# Selectric_Terminal.net
KiCad netlist of a schematic drawn in EasyEDA Pro
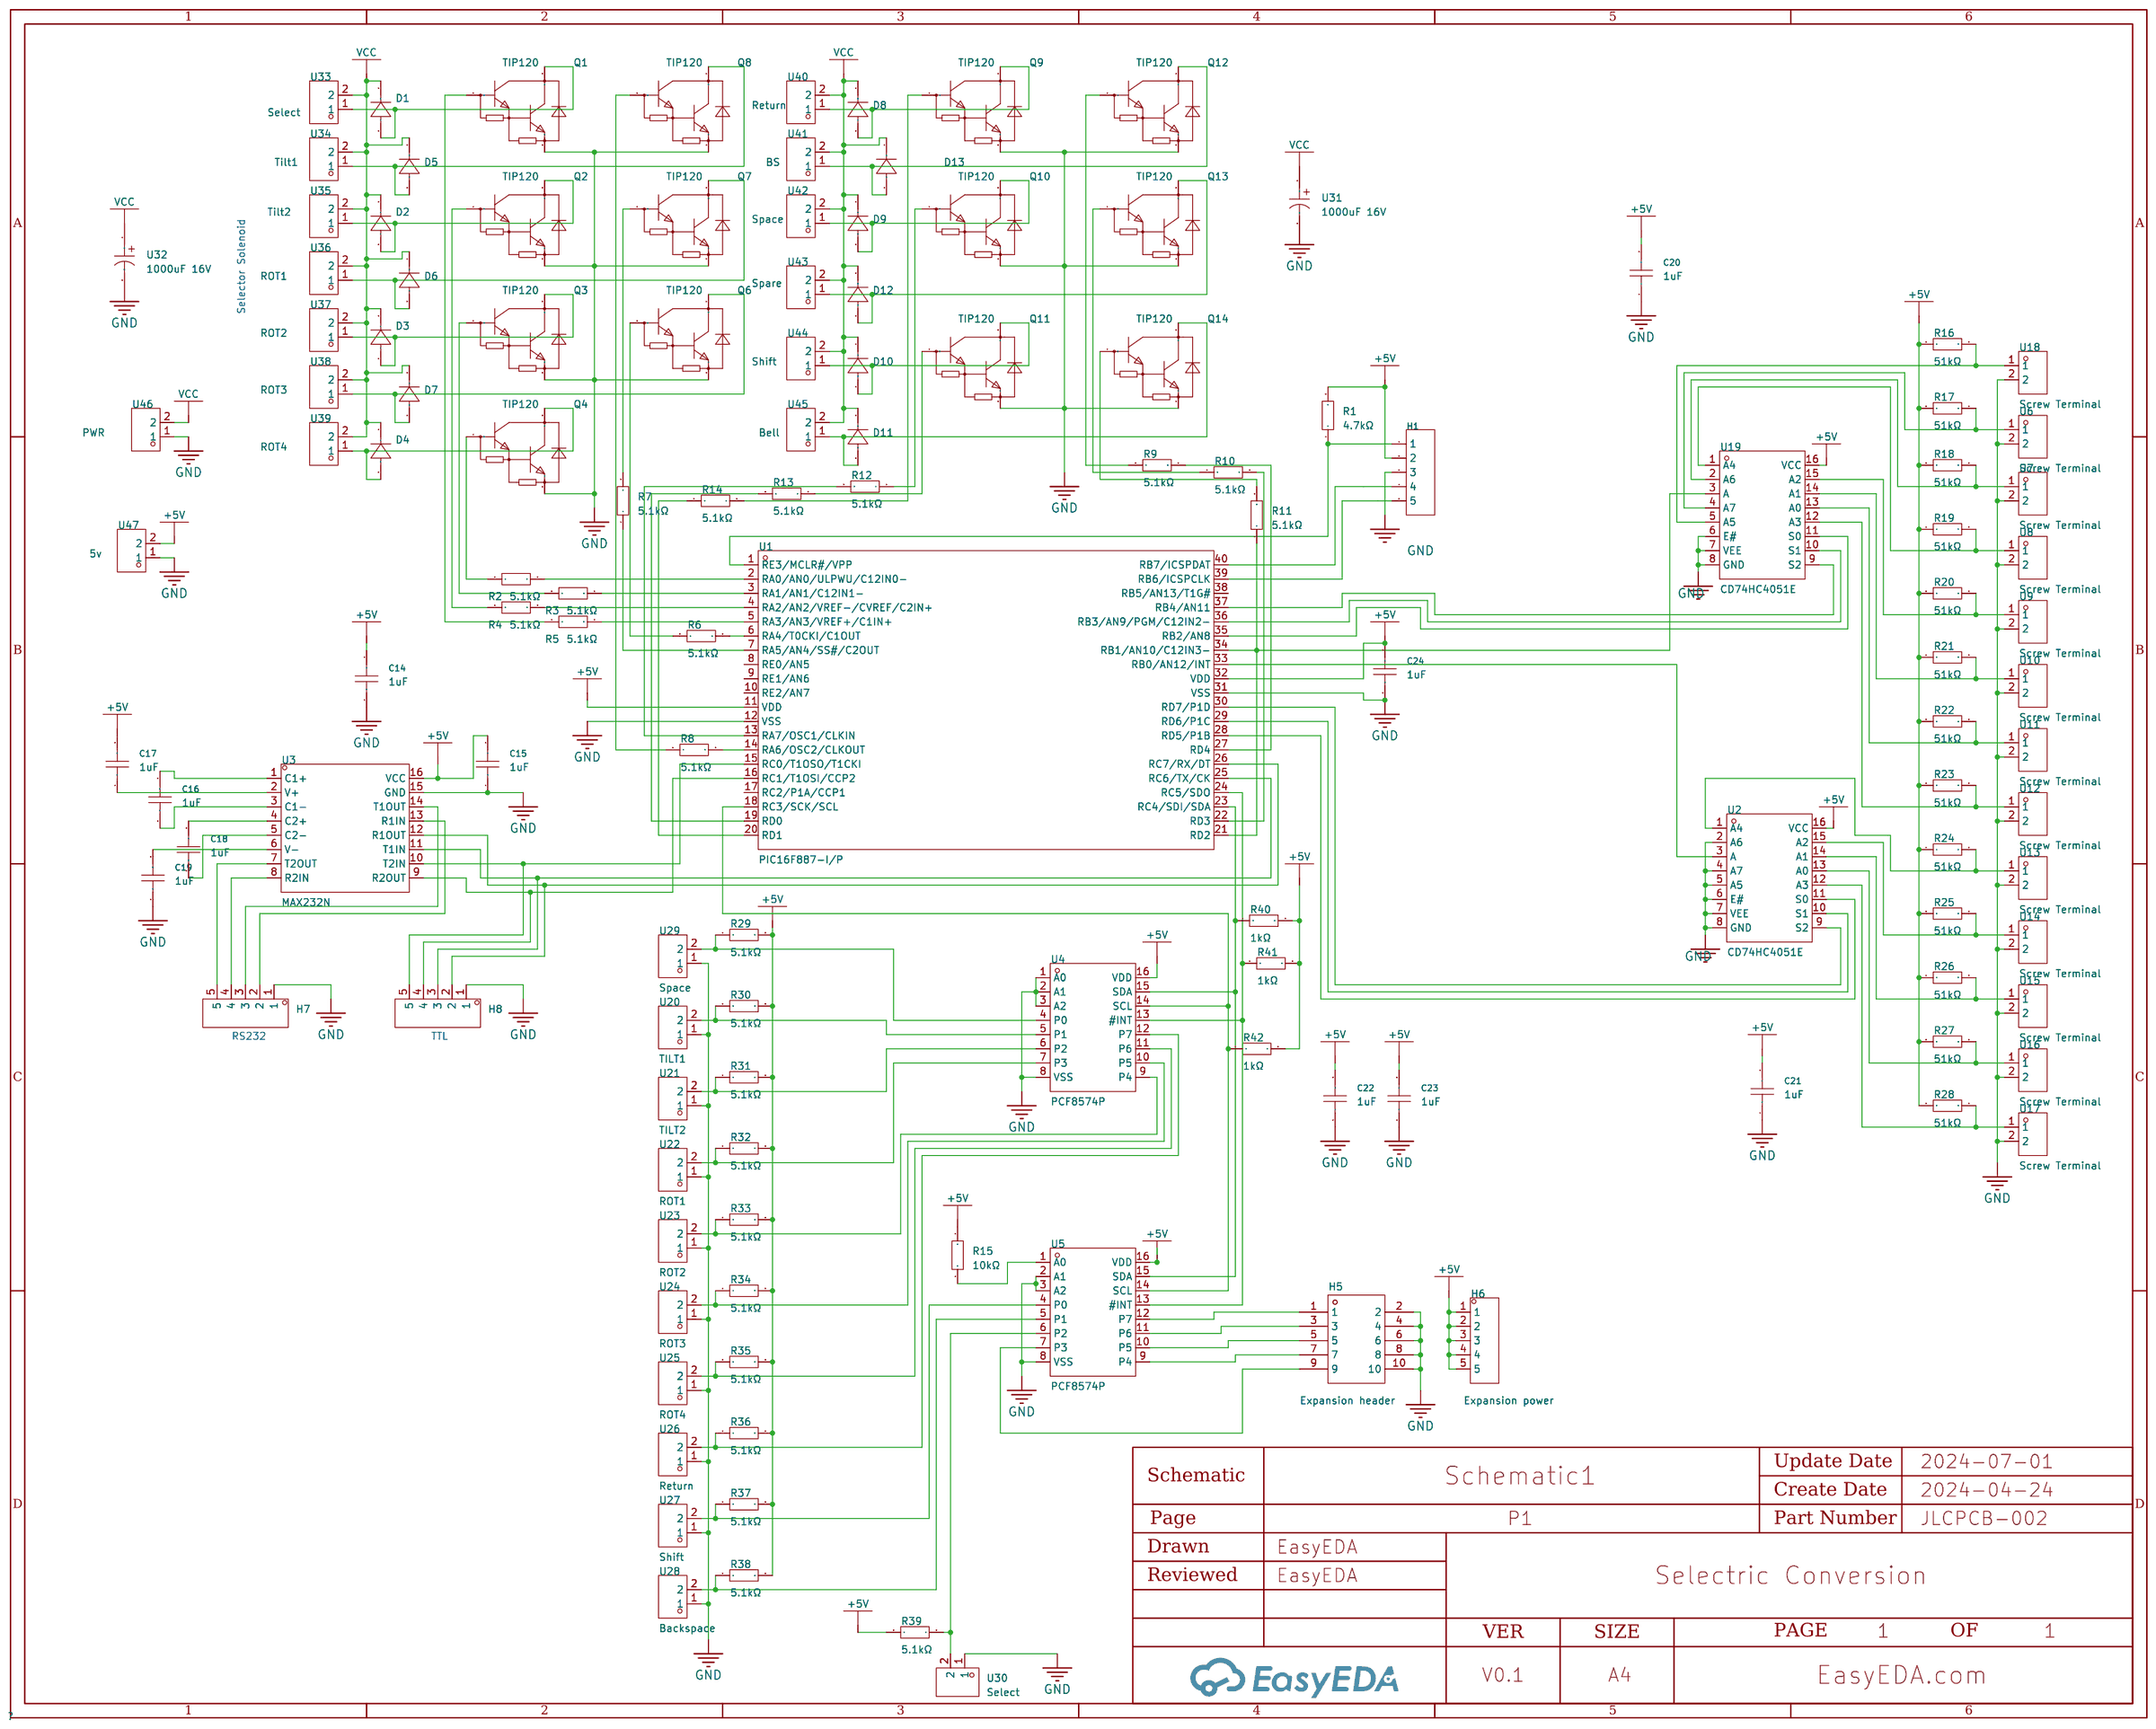
[diagram p0: schematic sheet]

(export (version "E")
  (design (tool "Eeschema 10.0.6"))
  (components
    (comp (ref "C14")
      (value "1uF")
      (footprint "easyedapro:CAP-TH_L5.0-W2.5-P5.00-D1.0")
      (fields
        (field (name "Manufacturer Part") "CC1H104MC1FD3F6C10MF")
        (field (name "Manufacturer") "Dersonic(德尔创)")
      )
      (libsource (lib "easyedapro") (part "CC1H104MC1FD3F6C10MF"))
    )
    (comp (ref "C15")
      (value "1uF")
      (footprint "easyedapro:CAP-TH_L5.0-W2.5-P5.00-D1.0")
      (fields
        (field (name "Manufacturer Part") "CC1H104MC1FD3F6C10MF")
        (field (name "Manufacturer") "Dersonic(德尔创)")
      )
      (libsource (lib "easyedapro") (part "CC1H104MC1FD3F6C10MF"))
    )
    (comp (ref "C16")
      (value "1uF")
      (footprint "easyedapro:CAP-TH_L5.0-W2.5-P5.00-D1.0")
      (fields
        (field (name "Manufacturer Part") "CC1H104MC1FD3F6C10MF")
        (field (name "Manufacturer") "Dersonic(德尔创)")
      )
      (libsource (lib "easyedapro") (part "CC1H104MC1FD3F6C10MF"))
    )
    (comp (ref "C17")
      (value "1uF")
      (footprint "easyedapro:CAP-TH_L5.0-W2.5-P5.00-D1.0")
      (fields
        (field (name "Manufacturer Part") "CC1H104MC1FD3F6C10MF")
        (field (name "Manufacturer") "Dersonic(德尔创)")
      )
      (libsource (lib "easyedapro") (part "CC1H104MC1FD3F6C10MF"))
    )
    (comp (ref "C18")
      (value "1uF")
      (footprint "easyedapro:CAP-TH_L5.0-W2.5-P5.00-D1.0")
      (fields
        (field (name "Manufacturer Part") "CC1H104MC1FD3F6C10MF")
        (field (name "Manufacturer") "Dersonic(德尔创)")
      )
      (libsource (lib "easyedapro") (part "CC1H104MC1FD3F6C10MF"))
    )
    (comp (ref "C19")
      (value "1uF")
      (footprint "easyedapro:CAP-TH_L5.0-W2.5-P5.00-D1.0")
      (fields
        (field (name "Manufacturer Part") "CC1H104MC1FD3F6C10MF")
        (field (name "Manufacturer") "Dersonic(德尔创)")
      )
      (libsource (lib "easyedapro") (part "CC1H104MC1FD3F6C10MF"))
    )
    (comp (ref "C20")
      (value "1uF")
      (footprint "easyedapro:CAP-TH_L5.0-W2.5-P5.00-D1.0")
      (fields
        (field (name "Manufacturer Part") "CC1H104MC1FD3F6C10MF")
        (field (name "Manufacturer") "Dersonic(德尔创)")
      )
      (libsource (lib "easyedapro") (part "CC1H104MC1FD3F6C10MF"))
    )
    (comp (ref "C21")
      (value "1uF")
      (footprint "easyedapro:CAP-TH_L5.0-W2.5-P5.00-D1.0")
      (fields
        (field (name "Manufacturer Part") "CC1H104MC1FD3F6C10MF")
        (field (name "Manufacturer") "Dersonic(德尔创)")
      )
      (libsource (lib "easyedapro") (part "CC1H104MC1FD3F6C10MF"))
    )
    (comp (ref "C22")
      (value "1uF")
      (footprint "easyedapro:CAP-TH_L5.0-W2.5-P5.00-D1.0")
      (fields
        (field (name "Manufacturer Part") "CC1H104MC1FD3F6C10MF")
        (field (name "Manufacturer") "Dersonic(德尔创)")
      )
      (libsource (lib "easyedapro") (part "CC1H104MC1FD3F6C10MF"))
    )
    (comp (ref "C23")
      (value "1uF")
      (footprint "easyedapro:CAP-TH_L5.0-W2.5-P5.00-D1.0")
      (fields
        (field (name "Manufacturer Part") "CC1H104MC1FD3F6C10MF")
        (field (name "Manufacturer") "Dersonic(德尔创)")
      )
      (libsource (lib "easyedapro") (part "CC1H104MC1FD3F6C10MF"))
    )
    (comp (ref "C24")
      (value "1uF")
      (footprint "easyedapro:CAP-TH_L5.0-W2.5-P5.00-D1.0")
      (fields
        (field (name "Manufacturer Part") "CC1H104MC1FD3F6C10MF")
        (field (name "Manufacturer") "Dersonic(德尔创)")
      )
      (libsource (lib "easyedapro") (part "CC1H104MC1FD3F6C10MF"))
    )
    (comp (ref "D1")
      (value "~")
      (footprint "easyedapro:DO-41_BD2.4-L4.7-P8.70-D0.9-RD")
      (libsource (lib "easyedapro") (part "D_1N4007"))
    )
    (comp (ref "D2")
      (value "~")
      (footprint "easyedapro:DO-41_BD2.4-L4.7-P8.70-D0.9-RD")
      (libsource (lib "easyedapro") (part "D_1N4007"))
    )
    (comp (ref "D3")
      (value "~")
      (footprint "easyedapro:DO-41_BD2.4-L4.7-P8.70-D0.9-RD")
      (libsource (lib "easyedapro") (part "D_1N4007"))
    )
    (comp (ref "D4")
      (value "~")
      (footprint "easyedapro:DO-41_BD2.4-L4.7-P8.70-D0.9-RD")
      (libsource (lib "easyedapro") (part "D_1N4007"))
    )
    (comp (ref "D5")
      (value "~")
      (footprint "easyedapro:DO-41_BD2.4-L4.7-P8.70-D0.9-RD")
      (libsource (lib "easyedapro") (part "D_1N4007"))
    )
    (comp (ref "D6")
      (value "~")
      (footprint "easyedapro:DO-41_BD2.4-L4.7-P8.70-D0.9-RD")
      (libsource (lib "easyedapro") (part "D_1N4007"))
    )
    (comp (ref "D7")
      (value "~")
      (footprint "easyedapro:DO-41_BD2.4-L4.7-P8.70-D0.9-RD")
      (libsource (lib "easyedapro") (part "D_1N4007"))
    )
    (comp (ref "D8")
      (value "~")
      (footprint "easyedapro:DO-41_BD2.4-L4.7-P8.70-D0.9-RD")
      (libsource (lib "easyedapro") (part "D_1N4007"))
    )
    (comp (ref "D9")
      (value "~")
      (footprint "easyedapro:DO-41_BD2.4-L4.7-P8.70-D0.9-RD")
      (libsource (lib "easyedapro") (part "D_1N4007"))
    )
    (comp (ref "D10")
      (value "~")
      (footprint "easyedapro:DO-41_BD2.4-L4.7-P8.70-D0.9-RD")
      (libsource (lib "easyedapro") (part "D_1N4007"))
    )
    (comp (ref "D11")
      (value "~")
      (footprint "easyedapro:DO-41_BD2.4-L4.7-P8.70-D0.9-RD")
      (libsource (lib "easyedapro") (part "D_1N4007"))
    )
    (comp (ref "D12")
      (value "~")
      (footprint "easyedapro:DO-41_BD2.4-L4.7-P8.70-D0.9-RD")
      (libsource (lib "easyedapro") (part "D_1N4007"))
    )
    (comp (ref "D13")
      (value "~")
      (footprint "easyedapro:DO-41_BD2.4-L4.7-P8.70-D0.9-RD")
      (libsource (lib "easyedapro") (part "D_1N4007"))
    )
    (comp (ref "H1")
      (value "~")
      (footprint "easyedapro:HDR-TH_5P-P2.54-V-F")
      (libsource (lib "easyedapro") (part "Header-Female-2.54_1x5"))
    )
    (comp (ref "H5")
      (value "Expansion header")
      (footprint "easyedapro:HDR-TH_10P-P2.54-V-M-R2-C5-S2.54")
      (libsource (lib "easyedapro") (part "HDR-M-2.54_2x5"))
    )
    (comp (ref "H6")
      (value "Expansion power")
      (footprint "easyedapro:HDR-TH_5P-P2.54-V-M")
      (libsource (lib "easyedapro") (part "MTP125-1105S1"))
    )
    (comp (ref "H7")
      (value "~")
      (footprint "easyedapro:HDR-TH_5P-P2.54-V-M")
      (libsource (lib "easyedapro") (part "MTP125-1105S1"))
    )
    (comp (ref "H8")
      (value "~")
      (footprint "easyedapro:HDR-TH_5P-P2.54-V-M")
      (libsource (lib "easyedapro") (part "MTP125-1105S1"))
    )
    (comp (ref "Q1")
      (value "TIP120")
      (footprint "easyedapro:TO-220-3_L10.0-W4.5-P2.54-L")
      (fields (field (name "Manufacturer") "ST(意法半导体)"))
      (libsource (lib "easyedapro") (part "TIP120"))
    )
    (comp (ref "Q2")
      (value "TIP120")
      (footprint "easyedapro:TO-220-3_L10.0-W4.5-P2.54-L")
      (fields (field (name "Manufacturer") "ST(意法半导体)"))
      (libsource (lib "easyedapro") (part "TIP120"))
    )
    (comp (ref "Q3")
      (value "TIP120")
      (footprint "easyedapro:TO-220-3_L10.0-W4.5-P2.54-L")
      (fields (field (name "Manufacturer") "ST(意法半导体)"))
      (libsource (lib "easyedapro") (part "TIP120"))
    )
    (comp (ref "Q4")
      (value "TIP120")
      (footprint "easyedapro:TO-220-3_L10.0-W4.5-P2.54-L")
      (fields (field (name "Manufacturer") "ST(意法半导体)"))
      (libsource (lib "easyedapro") (part "TIP120"))
    )
    (comp (ref "Q6")
      (value "TIP120")
      (footprint "easyedapro:TO-220-3_L10.0-W4.5-P2.54-L")
      (fields (field (name "Manufacturer") "ST(意法半导体)"))
      (libsource (lib "easyedapro") (part "TIP120"))
    )
    (comp (ref "Q7")
      (value "TIP120")
      (footprint "easyedapro:TO-220-3_L10.0-W4.5-P2.54-L")
      (fields (field (name "Manufacturer") "ST(意法半导体)"))
      (libsource (lib "easyedapro") (part "TIP120"))
    )
    (comp (ref "Q8")
      (value "TIP120")
      (footprint "easyedapro:TO-220-3_L10.0-W4.5-P2.54-L")
      (fields (field (name "Manufacturer") "ST(意法半导体)"))
      (libsource (lib "easyedapro") (part "TIP120"))
    )
    (comp (ref "Q9")
      (value "TIP120")
      (footprint "easyedapro:TO-220-3_L10.0-W4.5-P2.54-L")
      (fields (field (name "Manufacturer") "ST(意法半导体)"))
      (libsource (lib "easyedapro") (part "TIP120"))
    )
    (comp (ref "Q10")
      (value "TIP120")
      (footprint "easyedapro:TO-220-3_L10.0-W4.5-P2.54-L")
      (fields (field (name "Manufacturer") "ST(意法半导体)"))
      (libsource (lib "easyedapro") (part "TIP120"))
    )
    (comp (ref "Q11")
      (value "TIP120")
      (footprint "easyedapro:TO-220-3_L10.0-W4.5-P2.54-L")
      (fields (field (name "Manufacturer") "ST(意法半导体)"))
      (libsource (lib "easyedapro") (part "TIP120"))
    )
    (comp (ref "Q12")
      (value "TIP120")
      (footprint "easyedapro:TO-220-3_L10.0-W4.5-P2.54-L")
      (fields (field (name "Manufacturer") "ST(意法半导体)"))
      (libsource (lib "easyedapro") (part "TIP120"))
    )
    (comp (ref "Q13")
      (value "TIP120")
      (footprint "easyedapro:TO-220-3_L10.0-W4.5-P2.54-L")
      (fields (field (name "Manufacturer") "ST(意法半导体)"))
      (libsource (lib "easyedapro") (part "TIP120"))
    )
    (comp (ref "Q14")
      (value "TIP120")
      (footprint "easyedapro:TO-220-3_L10.0-W4.5-P2.54-L")
      (fields (field (name "Manufacturer") "ST(意法半导体)"))
      (libsource (lib "easyedapro") (part "TIP120"))
    )
    (comp (ref "R1")
      (value "4.7kΩ")
      (footprint "easyedapro:R_AXIAL-0.4")
      (libsource (lib "easyedapro") (part "Res"))
    )
    (comp (ref "R2")
      (value "5.1kΩ")
      (footprint "easyedapro:R_AXIAL-0.4")
      (libsource (lib "easyedapro") (part "Res"))
    )
    (comp (ref "R3")
      (value "5.1kΩ")
      (footprint "easyedapro:R_AXIAL-0.4")
      (libsource (lib "easyedapro") (part "Res"))
    )
    (comp (ref "R4")
      (value "5.1kΩ")
      (footprint "easyedapro:R_AXIAL-0.4")
      (libsource (lib "easyedapro") (part "Res"))
    )
    (comp (ref "R5")
      (value "5.1kΩ")
      (footprint "easyedapro:R_AXIAL-0.4")
      (libsource (lib "easyedapro") (part "Res"))
    )
    (comp (ref "R6")
      (value "5.1kΩ")
      (footprint "easyedapro:R_AXIAL-0.4")
      (libsource (lib "easyedapro") (part "Res"))
    )
    (comp (ref "R7")
      (value "5.1kΩ")
      (footprint "easyedapro:R_AXIAL-0.4")
      (libsource (lib "easyedapro") (part "Res"))
    )
    (comp (ref "R8")
      (value "5.1kΩ")
      (footprint "easyedapro:R_AXIAL-0.4")
      (libsource (lib "easyedapro") (part "Res"))
    )
    (comp (ref "R9")
      (value "5.1kΩ")
      (footprint "easyedapro:R_AXIAL-0.4")
      (libsource (lib "easyedapro") (part "Res"))
    )
    (comp (ref "R10")
      (value "5.1kΩ")
      (footprint "easyedapro:R_AXIAL-0.4")
      (libsource (lib "easyedapro") (part "Res"))
    )
    (comp (ref "R11")
      (value "5.1kΩ")
      (footprint "easyedapro:R_AXIAL-0.4")
      (libsource (lib "easyedapro") (part "Res"))
    )
    (comp (ref "R12")
      (value "5.1kΩ")
      (footprint "easyedapro:R_AXIAL-0.4")
      (libsource (lib "easyedapro") (part "Res"))
    )
    (comp (ref "R13")
      (value "5.1kΩ")
      (footprint "easyedapro:R_AXIAL-0.4")
      (libsource (lib "easyedapro") (part "Res"))
    )
    (comp (ref "R14")
      (value "5.1kΩ")
      (footprint "easyedapro:R_AXIAL-0.4")
      (libsource (lib "easyedapro") (part "Res"))
    )
    (comp (ref "R15")
      (value "10kΩ")
      (footprint "easyedapro:R_AXIAL-0.4")
      (libsource (lib "easyedapro") (part "Res"))
    )
    (comp (ref "R16")
      (value "51kΩ")
      (footprint "easyedapro:R_AXIAL-0.4")
      (libsource (lib "easyedapro") (part "Res"))
    )
    (comp (ref "R17")
      (value "51kΩ")
      (footprint "easyedapro:R_AXIAL-0.4")
      (libsource (lib "easyedapro") (part "Res"))
    )
    (comp (ref "R18")
      (value "51kΩ")
      (footprint "easyedapro:R_AXIAL-0.4")
      (libsource (lib "easyedapro") (part "Res"))
    )
    (comp (ref "R19")
      (value "51kΩ")
      (footprint "easyedapro:R_AXIAL-0.4")
      (libsource (lib "easyedapro") (part "Res"))
    )
    (comp (ref "R20")
      (value "51kΩ")
      (footprint "easyedapro:R_AXIAL-0.4")
      (libsource (lib "easyedapro") (part "Res"))
    )
    (comp (ref "R21")
      (value "51kΩ")
      (footprint "easyedapro:R_AXIAL-0.4")
      (libsource (lib "easyedapro") (part "Res"))
    )
    (comp (ref "R22")
      (value "51kΩ")
      (footprint "easyedapro:R_AXIAL-0.4")
      (libsource (lib "easyedapro") (part "Res"))
    )
    (comp (ref "R23")
      (value "51kΩ")
      (footprint "easyedapro:R_AXIAL-0.4")
      (libsource (lib "easyedapro") (part "Res"))
    )
    (comp (ref "R24")
      (value "51kΩ")
      (footprint "easyedapro:R_AXIAL-0.4")
      (libsource (lib "easyedapro") (part "Res"))
    )
    (comp (ref "R25")
      (value "51kΩ")
      (footprint "easyedapro:R_AXIAL-0.4")
      (libsource (lib "easyedapro") (part "Res"))
    )
    (comp (ref "R26")
      (value "51kΩ")
      (footprint "easyedapro:R_AXIAL-0.4")
      (libsource (lib "easyedapro") (part "Res"))
    )
    (comp (ref "R27")
      (value "51kΩ")
      (footprint "easyedapro:R_AXIAL-0.4")
      (libsource (lib "easyedapro") (part "Res"))
    )
    (comp (ref "R28")
      (value "51kΩ")
      (footprint "easyedapro:R_AXIAL-0.4")
      (libsource (lib "easyedapro") (part "Res"))
    )
    (comp (ref "R29")
      (value "5.1kΩ")
      (footprint "easyedapro:R_AXIAL-0.4")
      (libsource (lib "easyedapro") (part "Res"))
    )
    (comp (ref "R30")
      (value "5.1kΩ")
      (footprint "easyedapro:R_AXIAL-0.4")
      (libsource (lib "easyedapro") (part "Res"))
    )
    (comp (ref "R31")
      (value "5.1kΩ")
      (footprint "easyedapro:R_AXIAL-0.4")
      (libsource (lib "easyedapro") (part "Res"))
    )
    (comp (ref "R32")
      (value "5.1kΩ")
      (footprint "easyedapro:R_AXIAL-0.4")
      (libsource (lib "easyedapro") (part "Res"))
    )
    (comp (ref "R33")
      (value "5.1kΩ")
      (footprint "easyedapro:R_AXIAL-0.4")
      (libsource (lib "easyedapro") (part "Res"))
    )
    (comp (ref "R34")
      (value "5.1kΩ")
      (footprint "easyedapro:R_AXIAL-0.4")
      (libsource (lib "easyedapro") (part "Res"))
    )
    (comp (ref "R35")
      (value "5.1kΩ")
      (footprint "easyedapro:R_AXIAL-0.4")
      (libsource (lib "easyedapro") (part "Res"))
    )
    (comp (ref "R36")
      (value "5.1kΩ")
      (footprint "easyedapro:R_AXIAL-0.4")
      (libsource (lib "easyedapro") (part "Res"))
    )
    (comp (ref "R37")
      (value "5.1kΩ")
      (footprint "easyedapro:R_AXIAL-0.4")
      (libsource (lib "easyedapro") (part "Res"))
    )
    (comp (ref "R38")
      (value "5.1kΩ")
      (footprint "easyedapro:R_AXIAL-0.4")
      (libsource (lib "easyedapro") (part "Res"))
    )
    (comp (ref "R39")
      (value "5.1kΩ")
      (footprint "easyedapro:R_AXIAL-0.4")
      (libsource (lib "easyedapro") (part "Res"))
    )
    (comp (ref "R40")
      (value "1kΩ")
      (footprint "easyedapro:R_AXIAL-0.4")
      (libsource (lib "easyedapro") (part "Res"))
    )
    (comp (ref "R41")
      (value "1kΩ")
      (footprint "easyedapro:R_AXIAL-0.4")
      (libsource (lib "easyedapro") (part "Res"))
    )
    (comp (ref "R42")
      (value "1kΩ")
      (footprint "easyedapro:R_AXIAL-0.4")
      (libsource (lib "easyedapro") (part "Res"))
    )
    (comp (ref "U1")
      (value "PIC16F887-I/P")
      (footprint "easyedapro:PDIP-40_L52.3-W13.7-P2.54-LS15.5-BL")
      (fields (field (name "Manufacturer") "MICROCHIP(美国微芯)"))
      (libsource (lib "easyedapro") (part "PIC16F887-I/P"))
    )
    (comp (ref "U2")
      (value "CD74HC4051E")
      (footprint "easyedapro:DIP-16_L20.0-W6.4-P2.54-LS7.6-BL")
      (description "Number of Channels:1 Supply Voltage:2V~6V Supply Voltage:2V~6V On-State Resistance (Max):130Ω")
      (fields (field (name "Manufacturer") "TI(德州仪器)"))
      (libsource (lib "easyedapro") (part "CD74HC4051E"))
    )
    (comp (ref "U3")
      (value "MAX232N")
      (footprint "easyedapro:PDIP-16_L19.7-W6.6-P2.54-LS7.8-BL")
      (fields (field (name "Manufacturer") "TI(德州仪器)"))
      (libsource (lib "easyedapro") (part "MAX232N"))
    )
    (comp (ref "U4")
      (value "PCF8574P")
      (footprint "easyedapro:DIP-16_L19.3-W6.4-P2.54-LS7.6-BL")
      (fields (field (name "Manufacturer") "HGSEMI(华冠)"))
      (libsource (lib "easyedapro") (part "PCF8574P"))
    )
    (comp (ref "U5")
      (value "PCF8574P")
      (footprint "easyedapro:DIP-16_L19.3-W6.4-P2.54-LS7.6-BL")
      (fields (field (name "Manufacturer") "HGSEMI(华冠)"))
      (libsource (lib "easyedapro") (part "PCF8574P"))
    )
    (comp (ref "U6")
      (value "Screw Terminal")
      (footprint "easyedapro:CONN-TH_2P-P5.00_DB128V-5.0-2P")
      (fields
        (field (name "Manufacturer Part") "DB128V-5.0-2P-GN-S")
        (field (name "Manufacturer") "DORABO(地博电气)")
      )
      (libsource (lib "easyedapro") (part "DB128V-5.0-2P"))
    )
    (comp (ref "U7")
      (value "Screw Terminal")
      (footprint "easyedapro:CONN-TH_2P-P5.00_DB128V-5.0-2P")
      (fields
        (field (name "Manufacturer Part") "DB128V-5.0-2P-GN-S")
        (field (name "Manufacturer") "DORABO(地博电气)")
      )
      (libsource (lib "easyedapro") (part "DB128V-5.0-2P"))
    )
    (comp (ref "U8")
      (value "Screw Terminal")
      (footprint "easyedapro:CONN-TH_2P-P5.00_DB128V-5.0-2P")
      (fields
        (field (name "Manufacturer Part") "DB128V-5.0-2P-GN-S")
        (field (name "Manufacturer") "DORABO(地博电气)")
      )
      (libsource (lib "easyedapro") (part "DB128V-5.0-2P"))
    )
    (comp (ref "U9")
      (value "Screw Terminal")
      (footprint "easyedapro:CONN-TH_2P-P5.00_DB128V-5.0-2P")
      (fields
        (field (name "Manufacturer Part") "DB128V-5.0-2P-GN-S")
        (field (name "Manufacturer") "DORABO(地博电气)")
      )
      (libsource (lib "easyedapro") (part "DB128V-5.0-2P"))
    )
    (comp (ref "U10")
      (value "Screw Terminal")
      (footprint "easyedapro:CONN-TH_2P-P5.00_DB128V-5.0-2P")
      (fields
        (field (name "Manufacturer Part") "DB128V-5.0-2P-GN-S")
        (field (name "Manufacturer") "DORABO(地博电气)")
      )
      (libsource (lib "easyedapro") (part "DB128V-5.0-2P"))
    )
    (comp (ref "U11")
      (value "Screw Terminal")
      (footprint "easyedapro:CONN-TH_2P-P5.00_DB128V-5.0-2P")
      (fields
        (field (name "Manufacturer Part") "DB128V-5.0-2P-GN-S")
        (field (name "Manufacturer") "DORABO(地博电气)")
      )
      (libsource (lib "easyedapro") (part "DB128V-5.0-2P"))
    )
    (comp (ref "U12")
      (value "Screw Terminal")
      (footprint "easyedapro:CONN-TH_2P-P5.00_DB128V-5.0-2P")
      (fields
        (field (name "Manufacturer Part") "DB128V-5.0-2P-GN-S")
        (field (name "Manufacturer") "DORABO(地博电气)")
      )
      (libsource (lib "easyedapro") (part "DB128V-5.0-2P"))
    )
    (comp (ref "U13")
      (value "Screw Terminal")
      (footprint "easyedapro:CONN-TH_2P-P5.00_DB128V-5.0-2P")
      (fields
        (field (name "Manufacturer Part") "DB128V-5.0-2P-GN-S")
        (field (name "Manufacturer") "DORABO(地博电气)")
      )
      (libsource (lib "easyedapro") (part "DB128V-5.0-2P"))
    )
    (comp (ref "U14")
      (value "Screw Terminal")
      (footprint "easyedapro:CONN-TH_2P-P5.00_DB128V-5.0-2P")
      (fields
        (field (name "Manufacturer Part") "DB128V-5.0-2P-GN-S")
        (field (name "Manufacturer") "DORABO(地博电气)")
      )
      (libsource (lib "easyedapro") (part "DB128V-5.0-2P"))
    )
    (comp (ref "U15")
      (value "Screw Terminal")
      (footprint "easyedapro:CONN-TH_2P-P5.00_DB128V-5.0-2P")
      (fields
        (field (name "Manufacturer Part") "DB128V-5.0-2P-GN-S")
        (field (name "Manufacturer") "DORABO(地博电气)")
      )
      (libsource (lib "easyedapro") (part "DB128V-5.0-2P"))
    )
    (comp (ref "U16")
      (value "Screw Terminal")
      (footprint "easyedapro:CONN-TH_2P-P5.00_DB128V-5.0-2P")
      (fields
        (field (name "Manufacturer Part") "DB128V-5.0-2P-GN-S")
        (field (name "Manufacturer") "DORABO(地博电气)")
      )
      (libsource (lib "easyedapro") (part "DB128V-5.0-2P"))
    )
    (comp (ref "U17")
      (value "Screw Terminal")
      (footprint "easyedapro:CONN-TH_2P-P5.00_DB128V-5.0-2P")
      (fields
        (field (name "Manufacturer Part") "DB128V-5.0-2P-GN-S")
        (field (name "Manufacturer") "DORABO(地博电气)")
      )
      (libsource (lib "easyedapro") (part "DB128V-5.0-2P"))
    )
    (comp (ref "U18")
      (value "Screw Terminal")
      (footprint "easyedapro:CONN-TH_2P-P5.00_DB128V-5.0-2P")
      (fields
        (field (name "Manufacturer Part") "DB128V-5.0-2P-GN-S")
        (field (name "Manufacturer") "DORABO(地博电气)")
      )
      (libsource (lib "easyedapro") (part "DB128V-5.0-2P"))
    )
    (comp (ref "U19")
      (value "CD74HC4051E")
      (footprint "easyedapro:DIP-16_L20.0-W6.4-P2.54-LS7.6-BL")
      (description "Number of Channels:1 Supply Voltage:2V~6V Supply Voltage:2V~6V On-State Resistance (Max):130Ω")
      (fields (field (name "Manufacturer") "TI(德州仪器)"))
      (libsource (lib "easyedapro") (part "CD74HC4051E"))
    )
    (comp (ref "U20")
      (value "TILT1")
      (footprint "easyedapro:CONN-TH_2P-P5.00_DB128V-5.0-2P")
      (fields
        (field (name "Manufacturer Part") "DB128V-5.0-2P-GN-S")
        (field (name "Manufacturer") "DORABO(地博电气)")
      )
      (libsource (lib "easyedapro") (part "DB128V-5.0-2P"))
    )
    (comp (ref "U21")
      (value "TILT2")
      (footprint "easyedapro:CONN-TH_2P-P5.00_DB128V-5.0-2P")
      (fields
        (field (name "Manufacturer Part") "DB128V-5.0-2P-GN-S")
        (field (name "Manufacturer") "DORABO(地博电气)")
      )
      (libsource (lib "easyedapro") (part "DB128V-5.0-2P"))
    )
    (comp (ref "U22")
      (value "ROT1")
      (footprint "easyedapro:CONN-TH_2P-P5.00_DB128V-5.0-2P")
      (fields
        (field (name "Manufacturer Part") "DB128V-5.0-2P-GN-S")
        (field (name "Manufacturer") "DORABO(地博电气)")
      )
      (libsource (lib "easyedapro") (part "DB128V-5.0-2P"))
    )
    (comp (ref "U23")
      (value "ROT2")
      (footprint "easyedapro:CONN-TH_2P-P5.00_DB128V-5.0-2P")
      (fields
        (field (name "Manufacturer Part") "DB128V-5.0-2P-GN-S")
        (field (name "Manufacturer") "DORABO(地博电气)")
      )
      (libsource (lib "easyedapro") (part "DB128V-5.0-2P"))
    )
    (comp (ref "U24")
      (value "ROT3")
      (footprint "easyedapro:CONN-TH_2P-P5.00_DB128V-5.0-2P")
      (fields
        (field (name "Manufacturer Part") "DB128V-5.0-2P-GN-S")
        (field (name "Manufacturer") "DORABO(地博电气)")
      )
      (libsource (lib "easyedapro") (part "DB128V-5.0-2P"))
    )
    (comp (ref "U25")
      (value "ROT4")
      (footprint "easyedapro:CONN-TH_2P-P5.00_DB128V-5.0-2P")
      (fields
        (field (name "Manufacturer Part") "DB128V-5.0-2P-GN-S")
        (field (name "Manufacturer") "DORABO(地博电气)")
      )
      (libsource (lib "easyedapro") (part "DB128V-5.0-2P"))
    )
    (comp (ref "U26")
      (value "Return")
      (footprint "easyedapro:CONN-TH_2P-P5.00_DB128V-5.0-2P")
      (fields
        (field (name "Manufacturer Part") "DB128V-5.0-2P-GN-S")
        (field (name "Manufacturer") "DORABO(地博电气)")
      )
      (libsource (lib "easyedapro") (part "DB128V-5.0-2P"))
    )
    (comp (ref "U27")
      (value "Shift")
      (footprint "easyedapro:CONN-TH_2P-P5.00_DB128V-5.0-2P")
      (fields
        (field (name "Manufacturer Part") "DB128V-5.0-2P-GN-S")
        (field (name "Manufacturer") "DORABO(地博电气)")
      )
      (libsource (lib "easyedapro") (part "DB128V-5.0-2P"))
    )
    (comp (ref "U28")
      (value "Backspace")
      (footprint "easyedapro:CONN-TH_2P-P5.00_DB128V-5.0-2P")
      (fields
        (field (name "Manufacturer Part") "DB128V-5.0-2P-GN-S")
        (field (name "Manufacturer") "DORABO(地博电气)")
      )
      (libsource (lib "easyedapro") (part "DB128V-5.0-2P"))
    )
    (comp (ref "U29")
      (value "Space")
      (footprint "easyedapro:CONN-TH_2P-P5.00_DB128V-5.0-2P")
      (fields
        (field (name "Manufacturer Part") "DB128V-5.0-2P-GN-S")
        (field (name "Manufacturer") "DORABO(地博电气)")
      )
      (libsource (lib "easyedapro") (part "DB128V-5.0-2P"))
    )
    (comp (ref "U30")
      (value "Select")
      (footprint "easyedapro:CONN-TH_2P-P5.00_DB128V-5.0-2P")
      (fields
        (field (name "Manufacturer Part") "DB128V-5.0-2P-GN-S")
        (field (name "Manufacturer") "DORABO(地博电气)")
      )
      (libsource (lib "easyedapro") (part "DB128V-5.0-2P"))
    )
    (comp (ref "U31")
      (value "1000uF 16V")
      (footprint "easyedapro:CAP-TH_BD10.0-P5.00-D0.6-FD")
      (fields (field (name "Manufacturer") "CX(承兴)"))
      (libsource (lib "easyedapro") (part "1000UF 16V_C439782"))
    )
    (comp (ref "U32")
      (value "1000uF 16V")
      (footprint "easyedapro:CAP-TH_BD10.0-P5.00-D0.6-FD")
      (fields (field (name "Manufacturer") "CX(承兴)"))
      (libsource (lib "easyedapro") (part "1000UF 16V_C439782"))
    )
    (comp (ref "U33")
      (value "Select")
      (footprint "easyedapro:CONN-TH_2P-P5.00_DB128V-5.0-2P")
      (fields
        (field (name "Manufacturer Part") "DB128V-5.0-2P-GN-S")
        (field (name "Manufacturer") "DORABO(地博电气)")
      )
      (libsource (lib "easyedapro") (part "DB128V-5.0-2P"))
    )
    (comp (ref "U34")
      (value "Tilt1")
      (footprint "easyedapro:CONN-TH_2P-P5.00_DB128V-5.0-2P")
      (fields
        (field (name "Manufacturer Part") "DB128V-5.0-2P-GN-S")
        (field (name "Manufacturer") "DORABO(地博电气)")
      )
      (libsource (lib "easyedapro") (part "DB128V-5.0-2P"))
    )
    (comp (ref "U35")
      (value "Tilt2")
      (footprint "easyedapro:CONN-TH_2P-P5.00_DB128V-5.0-2P")
      (fields
        (field (name "Manufacturer Part") "DB128V-5.0-2P-GN-S")
        (field (name "Manufacturer") "DORABO(地博电气)")
      )
      (libsource (lib "easyedapro") (part "DB128V-5.0-2P"))
    )
    (comp (ref "U36")
      (value "ROT1")
      (footprint "easyedapro:CONN-TH_2P-P5.00_DB128V-5.0-2P")
      (fields
        (field (name "Manufacturer Part") "DB128V-5.0-2P-GN-S")
        (field (name "Manufacturer") "DORABO(地博电气)")
      )
      (libsource (lib "easyedapro") (part "DB128V-5.0-2P"))
    )
    (comp (ref "U37")
      (value "ROT2")
      (footprint "easyedapro:CONN-TH_2P-P5.00_DB128V-5.0-2P")
      (fields
        (field (name "Manufacturer Part") "DB128V-5.0-2P-GN-S")
        (field (name "Manufacturer") "DORABO(地博电气)")
      )
      (libsource (lib "easyedapro") (part "DB128V-5.0-2P"))
    )
    (comp (ref "U38")
      (value "ROT3")
      (footprint "easyedapro:CONN-TH_2P-P5.00_DB128V-5.0-2P")
      (fields
        (field (name "Manufacturer Part") "DB128V-5.0-2P-GN-S")
        (field (name "Manufacturer") "DORABO(地博电气)")
      )
      (libsource (lib "easyedapro") (part "DB128V-5.0-2P"))
    )
    (comp (ref "U39")
      (value "ROT4")
      (footprint "easyedapro:CONN-TH_2P-P5.00_DB128V-5.0-2P")
      (fields
        (field (name "Manufacturer Part") "DB128V-5.0-2P-GN-S")
        (field (name "Manufacturer") "DORABO(地博电气)")
      )
      (libsource (lib "easyedapro") (part "DB128V-5.0-2P"))
    )
    (comp (ref "U40")
      (value "Return")
      (footprint "easyedapro:CONN-TH_2P-P5.00_DB128V-5.0-2P")
      (fields
        (field (name "Manufacturer Part") "DB128V-5.0-2P-GN-S")
        (field (name "Manufacturer") "DORABO(地博电气)")
      )
      (libsource (lib "easyedapro") (part "DB128V-5.0-2P"))
    )
    (comp (ref "U41")
      (value "BS")
      (footprint "easyedapro:CONN-TH_2P-P5.00_DB128V-5.0-2P")
      (fields
        (field (name "Manufacturer Part") "DB128V-5.0-2P-GN-S")
        (field (name "Manufacturer") "DORABO(地博电气)")
      )
      (libsource (lib "easyedapro") (part "DB128V-5.0-2P"))
    )
    (comp (ref "U42")
      (value "Space")
      (footprint "easyedapro:CONN-TH_2P-P5.00_DB128V-5.0-2P")
      (fields
        (field (name "Manufacturer Part") "DB128V-5.0-2P-GN-S")
        (field (name "Manufacturer") "DORABO(地博电气)")
      )
      (libsource (lib "easyedapro") (part "DB128V-5.0-2P"))
    )
    (comp (ref "U43")
      (value "Spare")
      (footprint "easyedapro:CONN-TH_2P-P5.00_DB128V-5.0-2P")
      (fields
        (field (name "Manufacturer Part") "DB128V-5.0-2P-GN-S")
        (field (name "Manufacturer") "DORABO(地博电气)")
      )
      (libsource (lib "easyedapro") (part "DB128V-5.0-2P"))
    )
    (comp (ref "U44")
      (value "Shift")
      (footprint "easyedapro:CONN-TH_2P-P5.00_DB128V-5.0-2P")
      (fields
        (field (name "Manufacturer Part") "DB128V-5.0-2P-GN-S")
        (field (name "Manufacturer") "DORABO(地博电气)")
      )
      (libsource (lib "easyedapro") (part "DB128V-5.0-2P"))
    )
    (comp (ref "U45")
      (value "Bell")
      (footprint "easyedapro:CONN-TH_2P-P5.00_DB128V-5.0-2P")
      (fields
        (field (name "Manufacturer Part") "DB128V-5.0-2P-GN-S")
        (field (name "Manufacturer") "DORABO(地博电气)")
      )
      (libsource (lib "easyedapro") (part "DB128V-5.0-2P"))
    )
    (comp (ref "U46")
      (value "PWR")
      (footprint "easyedapro:CONN-TH_2P-P5.00_DB128V-5.0-2P")
      (fields
        (field (name "Manufacturer Part") "DB128V-5.0-2P-GN-S")
        (field (name "Manufacturer") "DORABO(地博电气)")
      )
      (libsource (lib "easyedapro") (part "DB128V-5.0-2P"))
    )
    (comp (ref "U47")
      (value "5v")
      (footprint "easyedapro:CONN-TH_2P-P5.00_DB128V-5.0-2P")
      (fields
        (field (name "Manufacturer Part") "DB128V-5.0-2P-GN-S")
        (field (name "Manufacturer") "DORABO(地博电气)")
      )
      (libsource (lib "easyedapro") (part "DB128V-5.0-2P"))
    )
  )
  (nets
    (net (code "1") (name "+5V") (class "Default")
      (node (ref "C14") (pin "2") (pinfunction "2_2") (pintype "input"))
      (node (ref "C15") (pin "2") (pinfunction "2_2") (pintype "input"))
      (node (ref "C17") (pin "2") (pinfunction "2_2") (pintype "input"))
      (node (ref "C20") (pin "2") (pinfunction "2_2") (pintype "input"))
      (node (ref "C21") (pin "2") (pinfunction "2_2") (pintype "input"))
      (node (ref "C22") (pin "2") (pinfunction "2_2") (pintype "input"))
      (node (ref "C23") (pin "2") (pinfunction "2_2") (pintype "input"))
      (node (ref "C24") (pin "2") (pinfunction "2_2") (pintype "input"))
      (node (ref "H1") (pin "2") (pinfunction "2_2") (pintype "input"))
      (node (ref "H6") (pin "1") (pinfunction "1_1") (pintype "input"))
      (node (ref "H6") (pin "2") (pinfunction "2_2") (pintype "input"))
      (node (ref "H6") (pin "3") (pinfunction "3_3") (pintype "input"))
      (node (ref "H6") (pin "4") (pinfunction "4_4") (pintype "input"))
      (node (ref "H6") (pin "5") (pinfunction "5_5") (pintype "input"))
      (node (ref "R1") (pin "2") (pinfunction "2_2") (pintype "input"))
      (node (ref "R15") (pin "2") (pinfunction "2_2") (pintype "input"))
      (node (ref "R16") (pin "1") (pinfunction "1_1") (pintype "input"))
      (node (ref "R17") (pin "1") (pinfunction "1_1") (pintype "input"))
      (node (ref "R18") (pin "1") (pinfunction "1_1") (pintype "input"))
      (node (ref "R19") (pin "1") (pinfunction "1_1") (pintype "input"))
      (node (ref "R20") (pin "1") (pinfunction "1_1") (pintype "input"))
      (node (ref "R21") (pin "1") (pinfunction "1_1") (pintype "input"))
      (node (ref "R22") (pin "1") (pinfunction "1_1") (pintype "input"))
      (node (ref "R23") (pin "1") (pinfunction "1_1") (pintype "input"))
      (node (ref "R24") (pin "1") (pinfunction "1_1") (pintype "input"))
      (node (ref "R25") (pin "1") (pinfunction "1_1") (pintype "input"))
      (node (ref "R26") (pin "1") (pinfunction "1_1") (pintype "input"))
      (node (ref "R27") (pin "1") (pinfunction "1_1") (pintype "input"))
      (node (ref "R28") (pin "1") (pinfunction "1_1") (pintype "input"))
      (node (ref "R29") (pin "2") (pinfunction "2_2") (pintype "input"))
      (node (ref "R30") (pin "2") (pinfunction "2_2") (pintype "input"))
      (node (ref "R31") (pin "2") (pinfunction "2_2") (pintype "input"))
      (node (ref "R32") (pin "2") (pinfunction "2_2") (pintype "input"))
      (node (ref "R33") (pin "2") (pinfunction "2_2") (pintype "input"))
      (node (ref "R34") (pin "2") (pinfunction "2_2") (pintype "input"))
      (node (ref "R35") (pin "2") (pinfunction "2_2") (pintype "input"))
      (node (ref "R36") (pin "2") (pinfunction "2_2") (pintype "input"))
      (node (ref "R37") (pin "2") (pinfunction "2_2") (pintype "input"))
      (node (ref "R38") (pin "2") (pinfunction "2_2") (pintype "input"))
      (node (ref "R39") (pin "1") (pinfunction "1_1") (pintype "input"))
      (node (ref "R40") (pin "2") (pinfunction "2_2") (pintype "input"))
      (node (ref "R41") (pin "2") (pinfunction "2_2") (pintype "input"))
      (node (ref "R42") (pin "2") (pinfunction "2_2") (pintype "input"))
      (node (ref "U1") (pin "11") (pinfunction "VDD_11") (pintype "input"))
      (node (ref "U1") (pin "32") (pinfunction "VDD_32") (pintype "input"))
      (node (ref "U19") (pin "16") (pinfunction "VCC_16") (pintype "unspecified"))
      (node (ref "U2") (pin "16") (pinfunction "VCC_16") (pintype "unspecified"))
      (node (ref "U3") (pin "16") (pinfunction "VCC_16") (pintype "unspecified"))
      (node (ref "U4") (pin "16") (pinfunction "VDD_16") (pintype "input"))
      (node (ref "U47") (pin "2") (pinfunction "2_2") (pintype "unspecified"))
      (node (ref "U5") (pin "16") (pinfunction "VDD_16") (pintype "input"))
    )
    (net (code "2") (name "GND") (class "Default")
      (node (ref "C14") (pin "1") (pinfunction "1_1") (pintype "input"))
      (node (ref "C15") (pin "1") (pinfunction "1_1") (pintype "input"))
      (node (ref "C19") (pin "1") (pinfunction "1_1") (pintype "input"))
      (node (ref "C20") (pin "1") (pinfunction "1_1") (pintype "input"))
      (node (ref "C21") (pin "1") (pinfunction "1_1") (pintype "input"))
      (node (ref "C22") (pin "1") (pinfunction "1_1") (pintype "input"))
      (node (ref "C23") (pin "1") (pinfunction "1_1") (pintype "input"))
      (node (ref "C24") (pin "1") (pinfunction "1_1") (pintype "input"))
      (node (ref "H1") (pin "3") (pinfunction "3_3") (pintype "input"))
      (node (ref "H5") (pin "10") (pinfunction "10_10") (pintype "input"))
      (node (ref "H5") (pin "2") (pinfunction "2_2") (pintype "input"))
      (node (ref "H5") (pin "4") (pinfunction "4_4") (pintype "input"))
      (node (ref "H5") (pin "6") (pinfunction "6_6") (pintype "input"))
      (node (ref "H5") (pin "8") (pinfunction "8_8") (pintype "input"))
      (node (ref "H7") (pin "1") (pinfunction "1_1") (pintype "input"))
      (node (ref "H8") (pin "1") (pinfunction "1_1") (pintype "input"))
      (node (ref "Q1") (pin "3") (pinfunction "E_3") (pintype "input"))
      (node (ref "Q10") (pin "3") (pinfunction "E_3") (pintype "input"))
      (node (ref "Q11") (pin "3") (pinfunction "E_3") (pintype "input"))
      (node (ref "Q12") (pin "3") (pinfunction "E_3") (pintype "input"))
      (node (ref "Q13") (pin "3") (pinfunction "E_3") (pintype "input"))
      (node (ref "Q14") (pin "3") (pinfunction "E_3") (pintype "input"))
      (node (ref "Q2") (pin "3") (pinfunction "E_3") (pintype "input"))
      (node (ref "Q3") (pin "3") (pinfunction "E_3") (pintype "input"))
      (node (ref "Q4") (pin "3") (pinfunction "E_3") (pintype "input"))
      (node (ref "Q6") (pin "3") (pinfunction "E_3") (pintype "input"))
      (node (ref "Q7") (pin "3") (pinfunction "E_3") (pintype "input"))
      (node (ref "Q8") (pin "3") (pinfunction "E_3") (pintype "input"))
      (node (ref "Q9") (pin "3") (pinfunction "E_3") (pintype "input"))
      (node (ref "U1") (pin "12") (pinfunction "VSS_12") (pintype "input"))
      (node (ref "U1") (pin "31") (pinfunction "VSS_31") (pintype "input"))
      (node (ref "U10") (pin "2") (pinfunction "2_2") (pintype "unspecified"))
      (node (ref "U11") (pin "2") (pinfunction "2_2") (pintype "unspecified"))
      (node (ref "U12") (pin "2") (pinfunction "2_2") (pintype "unspecified"))
      (node (ref "U13") (pin "2") (pinfunction "2_2") (pintype "unspecified"))
      (node (ref "U14") (pin "2") (pinfunction "2_2") (pintype "unspecified"))
      (node (ref "U15") (pin "2") (pinfunction "2_2") (pintype "unspecified"))
      (node (ref "U16") (pin "2") (pinfunction "2_2") (pintype "unspecified"))
      (node (ref "U17") (pin "2") (pinfunction "2_2") (pintype "unspecified"))
      (node (ref "U18") (pin "2") (pinfunction "2_2") (pintype "unspecified"))
      (node (ref "U19") (pin "6") (pinfunction "E#_6") (pintype "unspecified"))
      (node (ref "U19") (pin "7") (pinfunction "VEE_7") (pintype "unspecified"))
      (node (ref "U19") (pin "8") (pinfunction "GND_8") (pintype "unspecified"))
      (node (ref "U2") (pin "2") (pinfunction "A6_2") (pintype "unspecified"))
      (node (ref "U2") (pin "4") (pinfunction "A7_4") (pintype "unspecified"))
      (node (ref "U2") (pin "5") (pinfunction "A5_5") (pintype "unspecified"))
      (node (ref "U2") (pin "6") (pinfunction "E#_6") (pintype "unspecified"))
      (node (ref "U2") (pin "7") (pinfunction "VEE_7") (pintype "unspecified"))
      (node (ref "U2") (pin "8") (pinfunction "GND_8") (pintype "unspecified"))
      (node (ref "U20") (pin "1") (pinfunction "1_1") (pintype "unspecified"))
      (node (ref "U21") (pin "1") (pinfunction "1_1") (pintype "unspecified"))
      (node (ref "U22") (pin "1") (pinfunction "1_1") (pintype "unspecified"))
      (node (ref "U23") (pin "1") (pinfunction "1_1") (pintype "unspecified"))
      (node (ref "U24") (pin "1") (pinfunction "1_1") (pintype "unspecified"))
      (node (ref "U25") (pin "1") (pinfunction "1_1") (pintype "unspecified"))
      (node (ref "U26") (pin "1") (pinfunction "1_1") (pintype "unspecified"))
      (node (ref "U27") (pin "1") (pinfunction "1_1") (pintype "unspecified"))
      (node (ref "U28") (pin "1") (pinfunction "1_1") (pintype "unspecified"))
      (node (ref "U29") (pin "1") (pinfunction "1_1") (pintype "unspecified"))
      (node (ref "U3") (pin "15") (pinfunction "GND_15") (pintype "unspecified"))
      (node (ref "U30") (pin "1") (pinfunction "1_1") (pintype "unspecified"))
      (node (ref "U31") (pin "2") (pinfunction "2_2") (pintype "input"))
      (node (ref "U32") (pin "2") (pinfunction "2_2") (pintype "input"))
      (node (ref "U4") (pin "1") (pinfunction "A0_1") (pintype "input"))
      (node (ref "U4") (pin "2") (pinfunction "A1_2") (pintype "input"))
      (node (ref "U4") (pin "3") (pinfunction "A2_3") (pintype "input"))
      (node (ref "U4") (pin "8") (pinfunction "VSS_8") (pintype "input"))
      (node (ref "U46") (pin "1") (pinfunction "1_1") (pintype "unspecified"))
      (node (ref "U47") (pin "1") (pinfunction "1_1") (pintype "unspecified"))
      (node (ref "U5") (pin "2") (pinfunction "A1_2") (pintype "input"))
      (node (ref "U5") (pin "3") (pinfunction "A2_3") (pintype "input"))
      (node (ref "U5") (pin "8") (pinfunction "VSS_8") (pintype "input"))
      (node (ref "U6") (pin "2") (pinfunction "2_2") (pintype "unspecified"))
      (node (ref "U7") (pin "2") (pinfunction "2_2") (pintype "unspecified"))
      (node (ref "U8") (pin "2") (pinfunction "2_2") (pintype "unspecified"))
      (node (ref "U9") (pin "2") (pinfunction "2_2") (pintype "unspecified"))
    )
    (net (code "3") (name "Net-(D1-A)") (class "Default")
      (node (ref "D1") (pin "2") (pinfunction "A_2") (pintype "input"))
      (node (ref "Q1") (pin "2") (pinfunction "C_2") (pintype "input"))
      (node (ref "U33") (pin "1") (pinfunction "1_1") (pintype "unspecified"))
    )
    (net (code "4") (name "Net-(D2-A)") (class "Default")
      (node (ref "D2") (pin "2") (pinfunction "A_2") (pintype "input"))
      (node (ref "Q2") (pin "2") (pinfunction "C_2") (pintype "input"))
      (node (ref "U35") (pin "1") (pinfunction "1_1") (pintype "unspecified"))
    )
    (net (code "5") (name "Net-(D3-A)") (class "Default")
      (node (ref "D3") (pin "2") (pinfunction "A_2") (pintype "input"))
      (node (ref "Q3") (pin "2") (pinfunction "C_2") (pintype "input"))
      (node (ref "U37") (pin "1") (pinfunction "1_1") (pintype "unspecified"))
    )
    (net (code "6") (name "Net-(D4-A)") (class "Default")
      (node (ref "D4") (pin "2") (pinfunction "A_2") (pintype "input"))
      (node (ref "Q4") (pin "2") (pinfunction "C_2") (pintype "input"))
      (node (ref "U39") (pin "1") (pinfunction "1_1") (pintype "unspecified"))
    )
    (net (code "7") (name "Net-(D5-A)") (class "Default")
      (node (ref "D5") (pin "2") (pinfunction "A_2") (pintype "input"))
      (node (ref "Q8") (pin "2") (pinfunction "C_2") (pintype "input"))
      (node (ref "U34") (pin "1") (pinfunction "1_1") (pintype "unspecified"))
    )
    (net (code "8") (name "Net-(D6-A)") (class "Default")
      (node (ref "D6") (pin "2") (pinfunction "A_2") (pintype "input"))
      (node (ref "Q7") (pin "2") (pinfunction "C_2") (pintype "input"))
      (node (ref "U36") (pin "1") (pinfunction "1_1") (pintype "unspecified"))
    )
    (net (code "9") (name "Net-(D7-A)") (class "Default")
      (node (ref "D7") (pin "2") (pinfunction "A_2") (pintype "input"))
      (node (ref "Q6") (pin "2") (pinfunction "C_2") (pintype "input"))
      (node (ref "U38") (pin "1") (pinfunction "1_1") (pintype "unspecified"))
    )
    (net (code "10") (name "Net-(D8-A)") (class "Default")
      (node (ref "D8") (pin "2") (pinfunction "A_2") (pintype "input"))
      (node (ref "Q9") (pin "2") (pinfunction "C_2") (pintype "input"))
      (node (ref "U40") (pin "1") (pinfunction "1_1") (pintype "unspecified"))
    )
    (net (code "11") (name "Net-(D9-A)") (class "Default")
      (node (ref "D9") (pin "2") (pinfunction "A_2") (pintype "input"))
      (node (ref "Q10") (pin "2") (pinfunction "C_2") (pintype "input"))
      (node (ref "U42") (pin "1") (pinfunction "1_1") (pintype "unspecified"))
    )
    (net (code "12") (name "Net-(D10-A)") (class "Default")
      (node (ref "D10") (pin "2") (pinfunction "A_2") (pintype "input"))
      (node (ref "Q11") (pin "2") (pinfunction "C_2") (pintype "input"))
      (node (ref "U44") (pin "1") (pinfunction "1_1") (pintype "unspecified"))
    )
    (net (code "13") (name "Net-(D11-A)") (class "Default")
      (node (ref "D11") (pin "2") (pinfunction "A_2") (pintype "input"))
      (node (ref "Q14") (pin "2") (pinfunction "C_2") (pintype "input"))
      (node (ref "U45") (pin "1") (pinfunction "1_1") (pintype "unspecified"))
    )
    (net (code "14") (name "Net-(D12-A)") (class "Default")
      (node (ref "D12") (pin "2") (pinfunction "A_2") (pintype "input"))
      (node (ref "Q13") (pin "2") (pinfunction "C_2") (pintype "input"))
      (node (ref "U43") (pin "1") (pinfunction "1_1") (pintype "unspecified"))
    )
    (net (code "15") (name "Net-(D13-A)") (class "Default")
      (node (ref "D13") (pin "2") (pinfunction "A_2") (pintype "input"))
      (node (ref "Q12") (pin "2") (pinfunction "C_2") (pintype "input"))
      (node (ref "U41") (pin "1") (pinfunction "1_1") (pintype "unspecified"))
    )
    (net (code "16") (name "Net-(Q1-B)") (class "Default")
      (node (ref "Q1") (pin "1") (pinfunction "B_1") (pintype "input"))
      (node (ref "R5") (pin "1") (pinfunction "1_1") (pintype "input"))
    )
    (net (code "17") (name "Net-(Q2-B)") (class "Default")
      (node (ref "Q2") (pin "1") (pinfunction "B_1") (pintype "input"))
      (node (ref "R4") (pin "1") (pinfunction "1_1") (pintype "input"))
    )
    (net (code "18") (name "Net-(Q3-B)") (class "Default")
      (node (ref "Q3") (pin "1") (pinfunction "B_1") (pintype "input"))
      (node (ref "R3") (pin "1") (pinfunction "1_1") (pintype "input"))
    )
    (net (code "19") (name "Net-(Q4-B)") (class "Default")
      (node (ref "Q4") (pin "1") (pinfunction "B_1") (pintype "input"))
      (node (ref "R2") (pin "1") (pinfunction "1_1") (pintype "input"))
    )
    (net (code "20") (name "Net-(Q6-B)") (class "Default")
      (node (ref "Q6") (pin "1") (pinfunction "B_1") (pintype "input"))
      (node (ref "R6") (pin "1") (pinfunction "1_1") (pintype "input"))
    )
    (net (code "21") (name "Net-(Q7-B)") (class "Default")
      (node (ref "Q7") (pin "1") (pinfunction "B_1") (pintype "input"))
      (node (ref "R7") (pin "2") (pinfunction "2_2") (pintype "input"))
    )
    (net (code "22") (name "Net-(Q8-B)") (class "Default")
      (node (ref "Q8") (pin "1") (pinfunction "B_1") (pintype "input"))
      (node (ref "R8") (pin "1") (pinfunction "1_1") (pintype "input"))
    )
    (net (code "23") (name "Net-(Q9-B)") (class "Default")
      (node (ref "Q9") (pin "1") (pinfunction "B_1") (pintype "input"))
      (node (ref "R14") (pin "1") (pinfunction "1_1") (pintype "input"))
    )
    (net (code "24") (name "Net-(Q10-B)") (class "Default")
      (node (ref "Q10") (pin "1") (pinfunction "B_1") (pintype "input"))
      (node (ref "R12") (pin "1") (pinfunction "1_1") (pintype "input"))
    )
    (net (code "25") (name "Net-(Q11-B)") (class "Default")
      (node (ref "Q11") (pin "1") (pinfunction "B_1") (pintype "input"))
      (node (ref "R13") (pin "1") (pinfunction "1_1") (pintype "input"))
    )
    (net (code "26") (name "Net-(Q12-B)") (class "Default")
      (node (ref "Q12") (pin "1") (pinfunction "B_1") (pintype "input"))
      (node (ref "R9") (pin "1") (pinfunction "1_1") (pintype "input"))
    )
    (net (code "27") (name "Net-(Q13-B)") (class "Default")
      (node (ref "Q13") (pin "1") (pinfunction "B_1") (pintype "input"))
      (node (ref "R10") (pin "1") (pinfunction "1_1") (pintype "input"))
    )
    (net (code "28") (name "Net-(Q14-B)") (class "Default")
      (node (ref "Q14") (pin "1") (pinfunction "B_1") (pintype "input"))
      (node (ref "R11") (pin "2") (pinfunction "2_2") (pintype "input"))
    )
    (net (code "29") (name "Net-(U1-RA0{slash}AN0{slash}ULPWU{slash}C12IN0-)") (class "Default")
      (node (ref "R2") (pin "2") (pinfunction "2_2") (pintype "input"))
      (node (ref "U1") (pin "2") (pinfunction "RA0/AN0/ULPWU/C12IN0-_2") (pintype "input"))
    )
    (net (code "30") (name "Net-(U1-RA1{slash}AN1{slash}C12IN1-)") (class "Default")
      (node (ref "R3") (pin "2") (pinfunction "2_2") (pintype "input"))
      (node (ref "U1") (pin "3") (pinfunction "RA1/AN1/C12IN1-_3") (pintype "input"))
    )
    (net (code "31") (name "Net-(U1-RA2{slash}AN2{slash}VREF-{slash}CVREF{slash}C2IN+)") (class "Default")
      (node (ref "R4") (pin "2") (pinfunction "2_2") (pintype "input"))
      (node (ref "U1") (pin "4") (pinfunction "RA2/AN2/VREF-/CVREF/C2IN+_4") (pintype "input"))
    )
    (net (code "32") (name "Net-(U1-RA3{slash}AN3{slash}VREF+{slash}C1IN+)") (class "Default")
      (node (ref "R5") (pin "2") (pinfunction "2_2") (pintype "input"))
      (node (ref "U1") (pin "5") (pinfunction "RA3/AN3/VREF+/C1IN+_5") (pintype "input"))
    )
    (net (code "33") (name "Net-(U1-RA4{slash}T0CKI{slash}C1OUT)") (class "Default")
      (node (ref "R6") (pin "2") (pinfunction "2_2") (pintype "input"))
      (node (ref "U1") (pin "6") (pinfunction "RA4/T0CKI/C1OUT_6") (pintype "input"))
    )
    (net (code "34") (name "Net-(U1-RA5{slash}AN4{slash}SS#{slash}C2OUT)") (class "Default")
      (node (ref "R7") (pin "1") (pinfunction "1_1") (pintype "input"))
      (node (ref "U1") (pin "7") (pinfunction "RA5/AN4/SS#/C2OUT_7") (pintype "input"))
    )
    (net (code "35") (name "Net-(U1-RA6{slash}OSC2{slash}CLKOUT)") (class "Default")
      (node (ref "R8") (pin "2") (pinfunction "2_2") (pintype "input"))
      (node (ref "U1") (pin "14") (pinfunction "RA6/OSC2/CLKOUT_14") (pintype "input"))
    )
    (net (code "36") (name "Net-(U1-RA7{slash}OSC1{slash}CLKIN)") (class "Default")
      (node (ref "R12") (pin "2") (pinfunction "2_2") (pintype "input"))
      (node (ref "U1") (pin "13") (pinfunction "RA7/OSC1/CLKIN_13") (pintype "input"))
    )
    (net (code "37") (name "Net-(U1-RB0{slash}AN12{slash}INT)") (class "Default")
      (node (ref "U1") (pin "33") (pinfunction "RB0/AN12/INT_33") (pintype "input"))
      (node (ref "U2") (pin "3") (pinfunction "A_3") (pintype "unspecified"))
    )
    (net (code "38") (name "Net-(U1-RB1{slash}AN10{slash}C12IN3-)") (class "Default")
      (node (ref "R11") (pin "1") (pinfunction "1_1") (pintype "input"))
      (node (ref "U1") (pin "21") (pinfunction "RD2_21") (pintype "input"))
      (node (ref "U1") (pin "34") (pinfunction "RB1/AN10/C12IN3-_34") (pintype "input"))
      (node (ref "U19") (pin "3") (pinfunction "A_3") (pintype "unspecified"))
    )
    (net (code "39") (name "Net-(U1-RB2{slash}AN8)") (class "Default")
      (node (ref "U1") (pin "35") (pinfunction "RB2/AN8_35") (pintype "input"))
      (node (ref "U19") (pin "11") (pinfunction "S0_11") (pintype "unspecified"))
    )
    (net (code "40") (name "Net-(U1-RB3{slash}AN9{slash}PGM{slash}C12IN2-)") (class "Default")
      (node (ref "U1") (pin "36") (pinfunction "RB3/AN9/PGM/C12IN2-_36") (pintype "input"))
      (node (ref "U19") (pin "10") (pinfunction "S1_10") (pintype "unspecified"))
    )
    (net (code "41") (name "Net-(U1-RB4{slash}AN11)") (class "Default")
      (node (ref "U1") (pin "37") (pinfunction "RB4/AN11_37") (pintype "input"))
      (node (ref "U19") (pin "9") (pinfunction "S2_9") (pintype "unspecified"))
    )
    (net (code "42") (name "Net-(U1-RB6{slash}ICSPCLK)") (class "Default")
      (node (ref "H1") (pin "5") (pinfunction "5_5") (pintype "input"))
      (node (ref "U1") (pin "39") (pinfunction "RB6/ICSPCLK_39") (pintype "input"))
    )
    (net (code "43") (name "Net-(U1-RB7{slash}ICSPDAT)") (class "Default")
      (node (ref "H1") (pin "4") (pinfunction "4_4") (pintype "input"))
      (node (ref "U1") (pin "40") (pinfunction "RB7/ICSPDAT_40") (pintype "input"))
    )
    (net (code "44") (name "Net-(U1-RC0{slash}T1OSO{slash}T1CKI)") (class "Default")
      (node (ref "H8") (pin "5") (pinfunction "5_5") (pintype "input"))
      (node (ref "U1") (pin "15") (pinfunction "RC0/T1OSO/T1CKI_15") (pintype "input"))
      (node (ref "U3") (pin "10") (pinfunction "T2IN_10") (pintype "unspecified"))
    )
    (net (code "45") (name "Net-(U1-RC1{slash}T1OSI{slash}CCP2)") (class "Default")
      (node (ref "H8") (pin "4") (pinfunction "4_4") (pintype "input"))
      (node (ref "U1") (pin "16") (pinfunction "RC1/T1OSI/CCP2_16") (pintype "input"))
      (node (ref "U3") (pin "9") (pinfunction "R2OUT_9") (pintype "unspecified"))
    )
    (net (code "46") (name "Net-(U1-RC3{slash}SCK{slash}SCL)") (class "Default")
      (node (ref "R42") (pin "1") (pinfunction "1_1") (pintype "input"))
      (node (ref "U1") (pin "18") (pinfunction "RC3/SCK/SCL_18") (pintype "input"))
      (node (ref "U4") (pin "14") (pinfunction "SCL_14") (pintype "input"))
      (node (ref "U5") (pin "14") (pinfunction "SCL_14") (pintype "input"))
    )
    (net (code "47") (name "Net-(U1-RC4{slash}SDI{slash}SDA)") (class "Default")
      (node (ref "R40") (pin "1") (pinfunction "1_1") (pintype "input"))
      (node (ref "U1") (pin "23") (pinfunction "RC4/SDI/SDA_23") (pintype "input"))
      (node (ref "U4") (pin "15") (pinfunction "SDA_15") (pintype "input"))
      (node (ref "U5") (pin "15") (pinfunction "SDA_15") (pintype "input"))
    )
    (net (code "48") (name "Net-(U1-RC5{slash}SDO)") (class "Default")
      (node (ref "R41") (pin "1") (pinfunction "1_1") (pintype "input"))
      (node (ref "U1") (pin "24") (pinfunction "RC5/SDO_24") (pintype "input"))
      (node (ref "U4") (pin "13") (pinfunction "#INT_13") (pintype "input"))
      (node (ref "U5") (pin "13") (pinfunction "#INT_13") (pintype "input"))
    )
    (net (code "49") (name "Net-(U1-RC6{slash}TX{slash}CK)") (class "Default")
      (node (ref "H8") (pin "3") (pinfunction "3_3") (pintype "input"))
      (node (ref "U1") (pin "25") (pinfunction "RC6/TX/CK_25") (pintype "input"))
      (node (ref "U3") (pin "11") (pinfunction "T1IN_11") (pintype "unspecified"))
    )
    (net (code "50") (name "Net-(U1-RC7{slash}RX{slash}DT)") (class "Default")
      (node (ref "H8") (pin "2") (pinfunction "2_2") (pintype "input"))
      (node (ref "U1") (pin "26") (pinfunction "RC7/RX/DT_26") (pintype "input"))
      (node (ref "U3") (pin "12") (pinfunction "R1OUT_12") (pintype "unspecified"))
    )
    (net (code "51") (name "Net-(U1-RD0)") (class "Default")
      (node (ref "R13") (pin "2") (pinfunction "2_2") (pintype "input"))
      (node (ref "U1") (pin "19") (pinfunction "RD0_19") (pintype "input"))
    )
    (net (code "52") (name "Net-(U1-RD1)") (class "Default")
      (node (ref "R14") (pin "2") (pinfunction "2_2") (pintype "input"))
      (node (ref "U1") (pin "20") (pinfunction "RD1_20") (pintype "input"))
    )
    (net (code "53") (name "Net-(U1-RD3)") (class "Default")
      (node (ref "R10") (pin "2") (pinfunction "2_2") (pintype "input"))
      (node (ref "U1") (pin "22") (pinfunction "RD3_22") (pintype "input"))
    )
    (net (code "54") (name "Net-(U1-RD4)") (class "Default")
      (node (ref "R9") (pin "2") (pinfunction "2_2") (pintype "input"))
      (node (ref "U1") (pin "27") (pinfunction "RD4_27") (pintype "input"))
    )
    (net (code "55") (name "Net-(U1-RD5{slash}P1B)") (class "Default")
      (node (ref "U1") (pin "28") (pinfunction "RD5/P1B_28") (pintype "input"))
      (node (ref "U2") (pin "11") (pinfunction "S0_11") (pintype "unspecified"))
    )
    (net (code "56") (name "Net-(U1-RD6{slash}P1C)") (class "Default")
      (node (ref "U1") (pin "29") (pinfunction "RD6/P1C_29") (pintype "input"))
      (node (ref "U2") (pin "10") (pinfunction "S1_10") (pintype "unspecified"))
    )
    (net (code "57") (name "Net-(U1-RD7{slash}P1D)") (class "Default")
      (node (ref "U1") (pin "30") (pinfunction "RD7/P1D_30") (pintype "input"))
      (node (ref "U2") (pin "9") (pinfunction "S2_9") (pintype "unspecified"))
    )
    (net (code "58") (name "Net-(U1-RE3{slash}MCLR#{slash}VPP)") (class "Default")
      (node (ref "H1") (pin "1") (pinfunction "1_1") (pintype "input"))
      (node (ref "R1") (pin "1") (pinfunction "1_1") (pintype "input"))
      (node (ref "U1") (pin "1") (pinfunction "RE3/MCLR#/VPP_1") (pintype "input"))
    )
    (net (code "59") (name "Net-(U2-A0)") (class "Default")
      (node (ref "R27") (pin "2") (pinfunction "2_2") (pintype "input"))
      (node (ref "U16") (pin "1") (pinfunction "1_1") (pintype "unspecified"))
      (node (ref "U2") (pin "13") (pinfunction "A0_13") (pintype "unspecified"))
    )
    (net (code "60") (name "Net-(U2-A1)") (class "Default")
      (node (ref "R26") (pin "2") (pinfunction "2_2") (pintype "input"))
      (node (ref "U15") (pin "1") (pinfunction "1_1") (pintype "unspecified"))
      (node (ref "U2") (pin "14") (pinfunction "A1_14") (pintype "unspecified"))
    )
    (net (code "61") (name "Net-(U2-A2)") (class "Default")
      (node (ref "R25") (pin "2") (pinfunction "2_2") (pintype "input"))
      (node (ref "U14") (pin "1") (pinfunction "1_1") (pintype "unspecified"))
      (node (ref "U2") (pin "15") (pinfunction "A2_15") (pintype "unspecified"))
    )
    (net (code "62") (name "Net-(U2-A3)") (class "Default")
      (node (ref "R28") (pin "2") (pinfunction "2_2") (pintype "input"))
      (node (ref "U17") (pin "1") (pinfunction "1_1") (pintype "unspecified"))
      (node (ref "U2") (pin "12") (pinfunction "A3_12") (pintype "unspecified"))
    )
    (net (code "63") (name "Net-(U2-A4)") (class "Default")
      (node (ref "R24") (pin "2") (pinfunction "2_2") (pintype "input"))
      (node (ref "U13") (pin "1") (pinfunction "1_1") (pintype "unspecified"))
      (node (ref "U2") (pin "1") (pinfunction "A4_1") (pintype "unspecified"))
    )
    (net (code "64") (name "Net-(U3-C1+)") (class "Default")
      (node (ref "C16") (pin "2") (pinfunction "2_2") (pintype "input"))
      (node (ref "U3") (pin "1") (pinfunction "C1+_1") (pintype "unspecified"))
    )
    (net (code "65") (name "Net-(U3-C1-)") (class "Default")
      (node (ref "C16") (pin "1") (pinfunction "1_1") (pintype "input"))
      (node (ref "U3") (pin "3") (pinfunction "C1-_3") (pintype "unspecified"))
    )
    (net (code "66") (name "Net-(U3-C2+)") (class "Default")
      (node (ref "C18") (pin "2") (pinfunction "2_2") (pintype "input"))
      (node (ref "U3") (pin "4") (pinfunction "C2+_4") (pintype "unspecified"))
    )
    (net (code "67") (name "Net-(U3-C2-)") (class "Default")
      (node (ref "C18") (pin "1") (pinfunction "1_1") (pintype "input"))
      (node (ref "U3") (pin "5") (pinfunction "C2-_5") (pintype "unspecified"))
    )
    (net (code "68") (name "Net-(U3-R1IN)") (class "Default")
      (node (ref "H7") (pin "2") (pinfunction "2_2") (pintype "input"))
      (node (ref "U3") (pin "13") (pinfunction "R1IN_13") (pintype "unspecified"))
    )
    (net (code "69") (name "Net-(U3-R2IN)") (class "Default")
      (node (ref "H7") (pin "4") (pinfunction "4_4") (pintype "input"))
      (node (ref "U3") (pin "8") (pinfunction "R2IN_8") (pintype "unspecified"))
    )
    (net (code "70") (name "Net-(U3-T1OUT)") (class "Default")
      (node (ref "H7") (pin "3") (pinfunction "3_3") (pintype "input"))
      (node (ref "U3") (pin "14") (pinfunction "T1OUT_14") (pintype "unspecified"))
    )
    (net (code "71") (name "Net-(U3-T2OUT)") (class "Default")
      (node (ref "H7") (pin "5") (pinfunction "5_5") (pintype "input"))
      (node (ref "U3") (pin "7") (pinfunction "T2OUT_7") (pintype "unspecified"))
    )
    (net (code "72") (name "Net-(U3-V+)") (class "Default")
      (node (ref "C17") (pin "1") (pinfunction "1_1") (pintype "input"))
      (node (ref "U3") (pin "2") (pinfunction "V+_2") (pintype "unspecified"))
    )
    (net (code "73") (name "Net-(U3-V-)") (class "Default")
      (node (ref "C19") (pin "2") (pinfunction "2_2") (pintype "input"))
      (node (ref "U3") (pin "6") (pinfunction "V-_6") (pintype "unspecified"))
    )
    (net (code "74") (name "Net-(U4-P0)") (class "Default")
      (node (ref "R29") (pin "1") (pinfunction "1_1") (pintype "input"))
      (node (ref "U29") (pin "2") (pinfunction "2_2") (pintype "unspecified"))
      (node (ref "U4") (pin "4") (pinfunction "P0_4") (pintype "input"))
    )
    (net (code "75") (name "Net-(U4-P1)") (class "Default")
      (node (ref "R30") (pin "1") (pinfunction "1_1") (pintype "input"))
      (node (ref "U20") (pin "2") (pinfunction "2_2") (pintype "unspecified"))
      (node (ref "U4") (pin "5") (pinfunction "P1_5") (pintype "input"))
    )
    (net (code "76") (name "Net-(U4-P2)") (class "Default")
      (node (ref "R31") (pin "1") (pinfunction "1_1") (pintype "input"))
      (node (ref "U21") (pin "2") (pinfunction "2_2") (pintype "unspecified"))
      (node (ref "U4") (pin "6") (pinfunction "P2_6") (pintype "input"))
    )
    (net (code "77") (name "Net-(U4-P3)") (class "Default")
      (node (ref "R32") (pin "1") (pinfunction "1_1") (pintype "input"))
      (node (ref "U22") (pin "2") (pinfunction "2_2") (pintype "unspecified"))
      (node (ref "U4") (pin "7") (pinfunction "P3_7") (pintype "input"))
    )
    (net (code "78") (name "Net-(U4-P4)") (class "Default")
      (node (ref "R33") (pin "1") (pinfunction "1_1") (pintype "input"))
      (node (ref "U23") (pin "2") (pinfunction "2_2") (pintype "unspecified"))
      (node (ref "U4") (pin "9") (pinfunction "P4_9") (pintype "input"))
    )
    (net (code "79") (name "Net-(U4-P5)") (class "Default")
      (node (ref "R34") (pin "1") (pinfunction "1_1") (pintype "input"))
      (node (ref "U24") (pin "2") (pinfunction "2_2") (pintype "unspecified"))
      (node (ref "U4") (pin "10") (pinfunction "P5_10") (pintype "input"))
    )
    (net (code "80") (name "Net-(U4-P6)") (class "Default")
      (node (ref "R35") (pin "1") (pinfunction "1_1") (pintype "input"))
      (node (ref "U25") (pin "2") (pinfunction "2_2") (pintype "unspecified"))
      (node (ref "U4") (pin "11") (pinfunction "P6_11") (pintype "input"))
    )
    (net (code "81") (name "Net-(U4-P7)") (class "Default")
      (node (ref "R36") (pin "1") (pinfunction "1_1") (pintype "input"))
      (node (ref "U26") (pin "2") (pinfunction "2_2") (pintype "unspecified"))
      (node (ref "U4") (pin "12") (pinfunction "P7_12") (pintype "input"))
    )
    (net (code "82") (name "Net-(U5-A0)") (class "Default")
      (node (ref "R15") (pin "1") (pinfunction "1_1") (pintype "input"))
      (node (ref "U5") (pin "1") (pinfunction "A0_1") (pintype "input"))
    )
    (net (code "83") (name "Net-(U5-P0)") (class "Default")
      (node (ref "R37") (pin "1") (pinfunction "1_1") (pintype "input"))
      (node (ref "U27") (pin "2") (pinfunction "2_2") (pintype "unspecified"))
      (node (ref "U5") (pin "4") (pinfunction "P0_4") (pintype "input"))
    )
    (net (code "84") (name "Net-(U5-P1)") (class "Default")
      (node (ref "R38") (pin "1") (pinfunction "1_1") (pintype "input"))
      (node (ref "U28") (pin "2") (pinfunction "2_2") (pintype "unspecified"))
      (node (ref "U5") (pin "5") (pinfunction "P1_5") (pintype "input"))
    )
    (net (code "85") (name "Net-(U5-P2)") (class "Default")
      (node (ref "R39") (pin "2") (pinfunction "2_2") (pintype "input"))
      (node (ref "U30") (pin "2") (pinfunction "2_2") (pintype "unspecified"))
      (node (ref "U5") (pin "6") (pinfunction "P2_6") (pintype "input"))
    )
    (net (code "86") (name "Net-(U5-P3)") (class "Default")
      (node (ref "H5") (pin "9") (pinfunction "9_9") (pintype "input"))
      (node (ref "U5") (pin "7") (pinfunction "P3_7") (pintype "input"))
    )
    (net (code "87") (name "Net-(U5-P4)") (class "Default")
      (node (ref "H5") (pin "7") (pinfunction "7_7") (pintype "input"))
      (node (ref "U5") (pin "9") (pinfunction "P4_9") (pintype "input"))
    )
    (net (code "88") (name "Net-(U5-P5)") (class "Default")
      (node (ref "H5") (pin "5") (pinfunction "5_5") (pintype "input"))
      (node (ref "U5") (pin "10") (pinfunction "P5_10") (pintype "input"))
    )
    (net (code "89") (name "Net-(U5-P6)") (class "Default")
      (node (ref "H5") (pin "3") (pinfunction "3_3") (pintype "input"))
      (node (ref "U5") (pin "11") (pinfunction "P6_11") (pintype "input"))
    )
    (net (code "90") (name "Net-(U5-P7)") (class "Default")
      (node (ref "H5") (pin "1") (pinfunction "1_1") (pintype "input"))
      (node (ref "U5") (pin "12") (pinfunction "P7_12") (pintype "input"))
    )
    (net (code "91") (name "Net-(U19-A0)") (class "Default")
      (node (ref "R22") (pin "2") (pinfunction "2_2") (pintype "input"))
      (node (ref "U11") (pin "1") (pinfunction "1_1") (pintype "unspecified"))
      (node (ref "U19") (pin "13") (pinfunction "A0_13") (pintype "unspecified"))
    )
    (net (code "92") (name "Net-(U19-A1)") (class "Default")
      (node (ref "R21") (pin "2") (pinfunction "2_2") (pintype "input"))
      (node (ref "U10") (pin "1") (pinfunction "1_1") (pintype "unspecified"))
      (node (ref "U19") (pin "14") (pinfunction "A1_14") (pintype "unspecified"))
    )
    (net (code "93") (name "Net-(U19-A2)") (class "Default")
      (node (ref "R20") (pin "2") (pinfunction "2_2") (pintype "input"))
      (node (ref "U19") (pin "15") (pinfunction "A2_15") (pintype "unspecified"))
      (node (ref "U9") (pin "1") (pinfunction "1_1") (pintype "unspecified"))
    )
    (net (code "94") (name "Net-(U19-A3)") (class "Default")
      (node (ref "R23") (pin "2") (pinfunction "2_2") (pintype "input"))
      (node (ref "U12") (pin "1") (pinfunction "1_1") (pintype "unspecified"))
      (node (ref "U19") (pin "12") (pinfunction "A3_12") (pintype "unspecified"))
    )
    (net (code "95") (name "Net-(U19-A4)") (class "Default")
      (node (ref "R19") (pin "2") (pinfunction "2_2") (pintype "input"))
      (node (ref "U19") (pin "1") (pinfunction "A4_1") (pintype "unspecified"))
      (node (ref "U8") (pin "1") (pinfunction "1_1") (pintype "unspecified"))
    )
    (net (code "96") (name "Net-(U19-A5)") (class "Default")
      (node (ref "R16") (pin "2") (pinfunction "2_2") (pintype "input"))
      (node (ref "U18") (pin "1") (pinfunction "1_1") (pintype "unspecified"))
      (node (ref "U19") (pin "5") (pinfunction "A5_5") (pintype "unspecified"))
    )
    (net (code "97") (name "Net-(U19-A6)") (class "Default")
      (node (ref "R18") (pin "2") (pinfunction "2_2") (pintype "input"))
      (node (ref "U19") (pin "2") (pinfunction "A6_2") (pintype "unspecified"))
      (node (ref "U7") (pin "1") (pinfunction "1_1") (pintype "unspecified"))
    )
    (net (code "98") (name "Net-(U19-A7)") (class "Default")
      (node (ref "R17") (pin "2") (pinfunction "2_2") (pintype "input"))
      (node (ref "U19") (pin "4") (pinfunction "A7_4") (pintype "unspecified"))
      (node (ref "U6") (pin "1") (pinfunction "1_1") (pintype "unspecified"))
    )
    (net (code "99") (name "VCC") (class "Default")
      (node (ref "D1") (pin "1") (pinfunction "K_1") (pintype "input"))
      (node (ref "D10") (pin "1") (pinfunction "K_1") (pintype "input"))
      (node (ref "D11") (pin "1") (pinfunction "K_1") (pintype "input"))
      (node (ref "D12") (pin "1") (pinfunction "K_1") (pintype "input"))
      (node (ref "D13") (pin "1") (pinfunction "K_1") (pintype "input"))
      (node (ref "D2") (pin "1") (pinfunction "K_1") (pintype "input"))
      (node (ref "D3") (pin "1") (pinfunction "K_1") (pintype "input"))
      (node (ref "D4") (pin "1") (pinfunction "K_1") (pintype "input"))
      (node (ref "D5") (pin "1") (pinfunction "K_1") (pintype "input"))
      (node (ref "D6") (pin "1") (pinfunction "K_1") (pintype "input"))
      (node (ref "D7") (pin "1") (pinfunction "K_1") (pintype "input"))
      (node (ref "D8") (pin "1") (pinfunction "K_1") (pintype "input"))
      (node (ref "D9") (pin "1") (pinfunction "K_1") (pintype "input"))
      (node (ref "U31") (pin "1") (pinfunction "1_1") (pintype "input"))
      (node (ref "U32") (pin "1") (pinfunction "1_1") (pintype "input"))
      (node (ref "U33") (pin "2") (pinfunction "2_2") (pintype "unspecified"))
      (node (ref "U34") (pin "2") (pinfunction "2_2") (pintype "unspecified"))
      (node (ref "U35") (pin "2") (pinfunction "2_2") (pintype "unspecified"))
      (node (ref "U36") (pin "2") (pinfunction "2_2") (pintype "unspecified"))
      (node (ref "U37") (pin "2") (pinfunction "2_2") (pintype "unspecified"))
      (node (ref "U38") (pin "2") (pinfunction "2_2") (pintype "unspecified"))
      (node (ref "U39") (pin "2") (pinfunction "2_2") (pintype "unspecified"))
      (node (ref "U40") (pin "2") (pinfunction "2_2") (pintype "unspecified"))
      (node (ref "U41") (pin "2") (pinfunction "2_2") (pintype "unspecified"))
      (node (ref "U42") (pin "2") (pinfunction "2_2") (pintype "unspecified"))
      (node (ref "U43") (pin "2") (pinfunction "2_2") (pintype "unspecified"))
      (node (ref "U44") (pin "2") (pinfunction "2_2") (pintype "unspecified"))
      (node (ref "U45") (pin "2") (pinfunction "2_2") (pintype "unspecified"))
      (node (ref "U46") (pin "2") (pinfunction "2_2") (pintype "unspecified"))
    )
    (net (code "100") (name "unconnected-(U1-RB5{slash}AN13{slash}T1G#-Pad38)") (class "Default")
      (node (ref "U1") (pin "38") (pinfunction "RB5/AN13/T1G#_38") (pintype "input"))
    )
    (net (code "101") (name "unconnected-(U1-RC2{slash}P1A{slash}CCP1-Pad17)") (class "Default")
      (node (ref "U1") (pin "17") (pinfunction "RC2/P1A/CCP1_17") (pintype "input"))
    )
    (net (code "102") (name "unconnected-(U1-RE0{slash}AN5-Pad8)") (class "Default")
      (node (ref "U1") (pin "8") (pinfunction "RE0/AN5_8") (pintype "input"))
    )
    (net (code "103") (name "unconnected-(U1-RE1{slash}AN6-Pad9)") (class "Default")
      (node (ref "U1") (pin "9") (pinfunction "RE1/AN6_9") (pintype "input"))
    )
    (net (code "104") (name "unconnected-(U1-RE2{slash}AN7-Pad10)") (class "Default")
      (node (ref "U1") (pin "10") (pinfunction "RE2/AN7_10") (pintype "input"))
    )
  )
)
